# 16_ch_sample-and-hold_card_v4_1_1.net
KiCad netlist of a schematic drawn in EAGLE
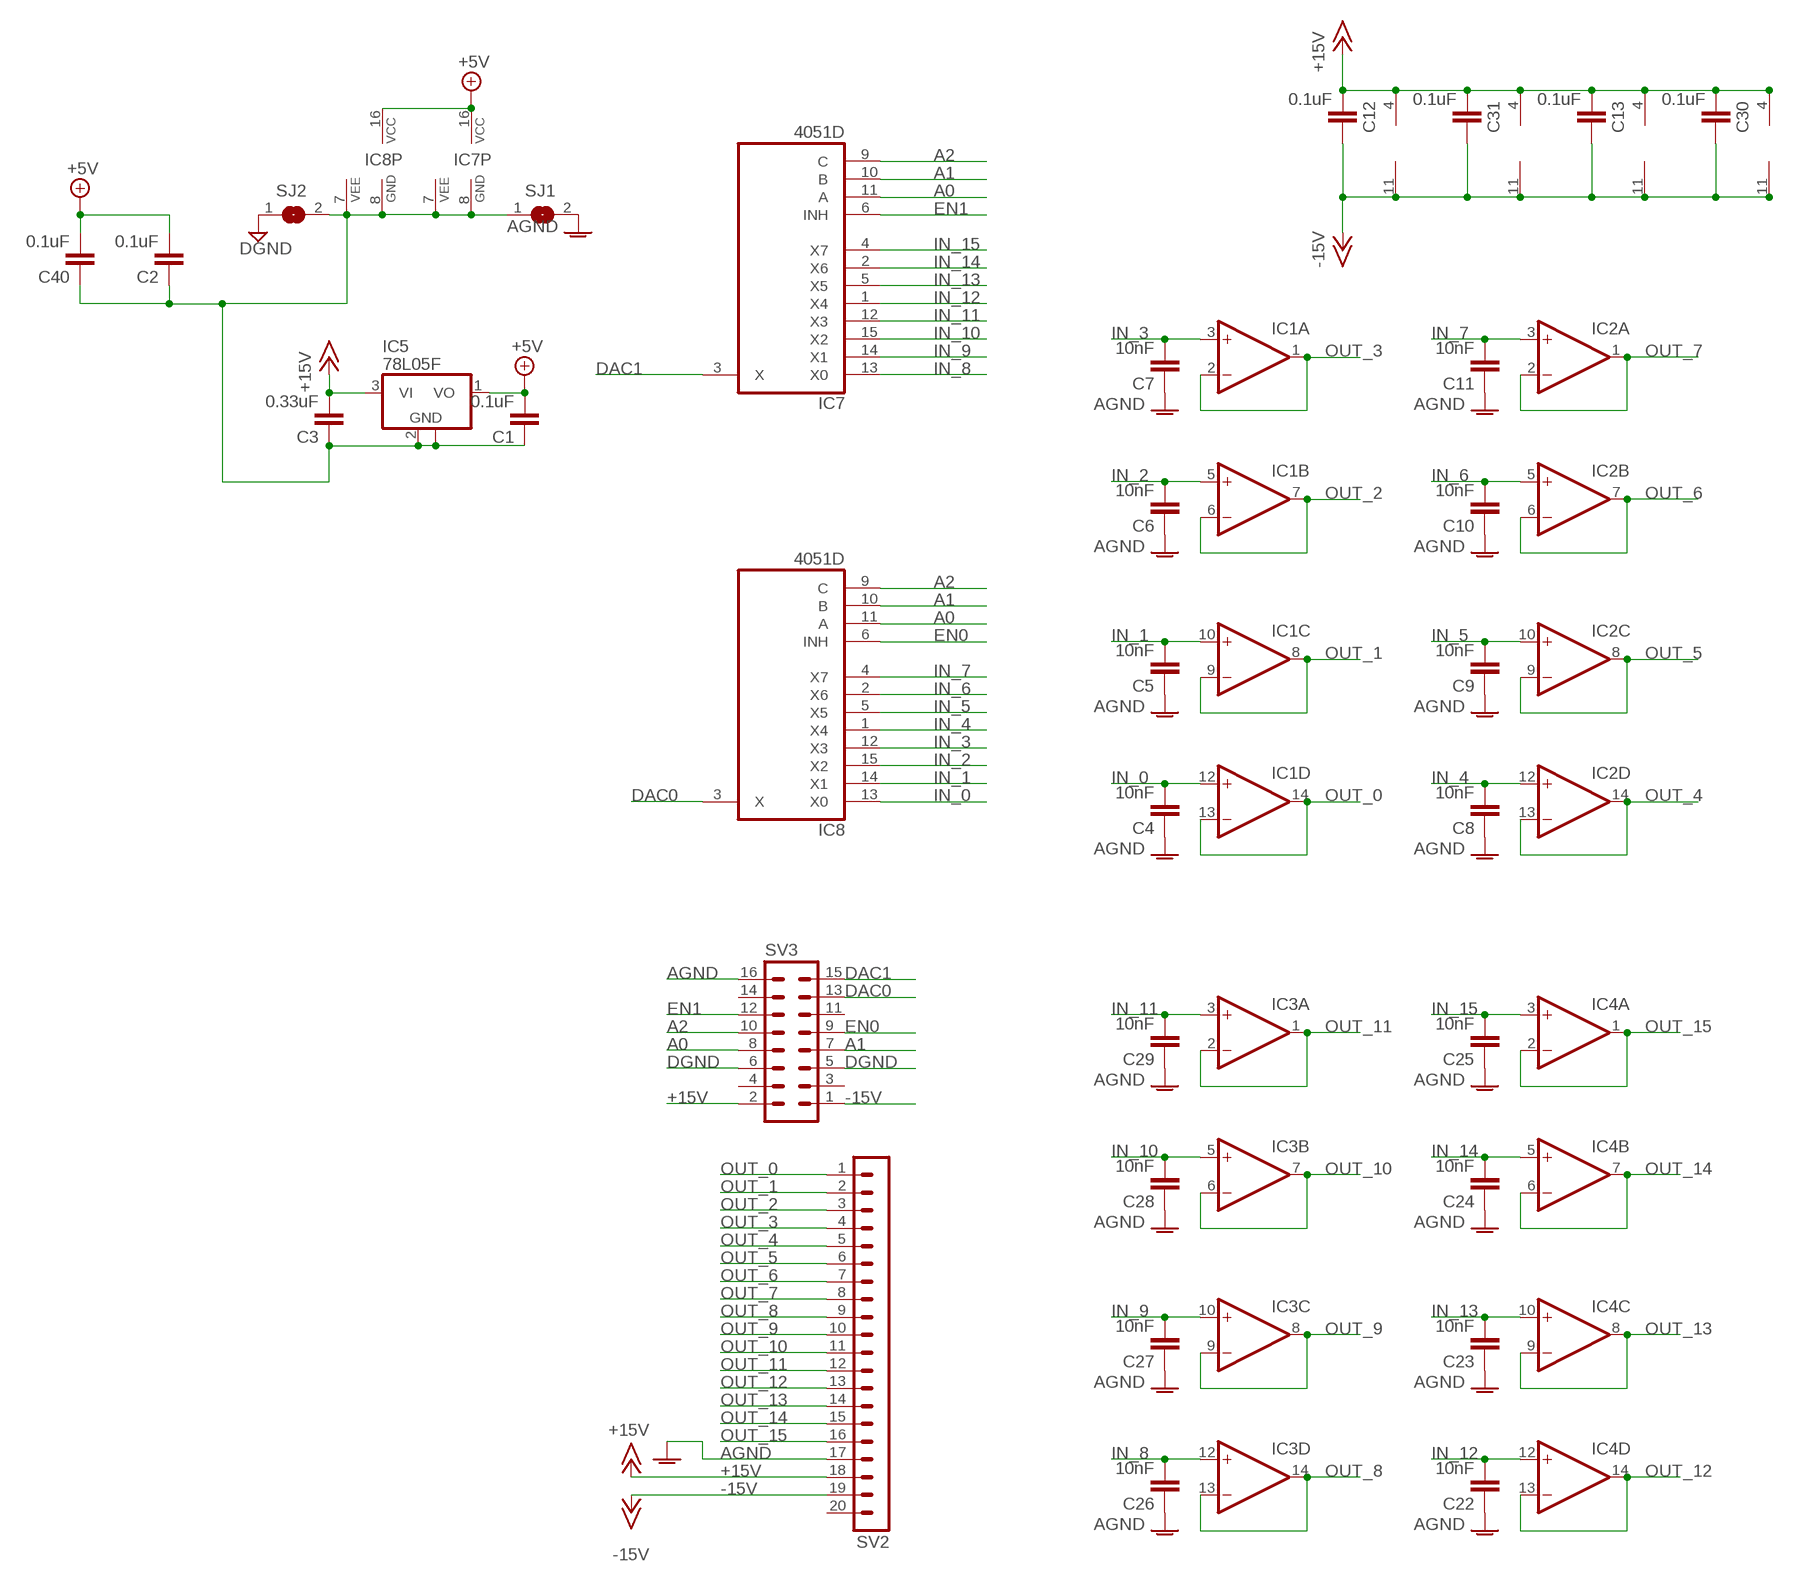
[diagram p0: schematic, sheet 1]

(export (version "E")
  (design (tool "Eeschema 10.0.6"))
  (components
    (comp (ref "C1")
      (value "0.1uF")
      (footprint "eagle-import:C0603")
      (libsource (lib "eagle-import") (part "resistor_C-EUC0603"))
    )
    (comp (ref "C2")
      (value "0.1uF")
      (footprint "eagle-import:C0603")
      (libsource (lib "eagle-import") (part "resistor_C-EUC0603"))
    )
    (comp (ref "C3")
      (value "0.33uF")
      (footprint "eagle-import:C0603")
      (libsource (lib "eagle-import") (part "resistor_C-EUC0603"))
    )
    (comp (ref "C4")
      (value "10nF")
      (footprint "eagle-import:C0805")
      (libsource (lib "eagle-import") (part "C-EUC0805"))
    )
    (comp (ref "C5")
      (value "10nF")
      (footprint "eagle-import:C0805")
      (libsource (lib "eagle-import") (part "C-EUC0805"))
    )
    (comp (ref "C6")
      (value "10nF")
      (footprint "eagle-import:C0805")
      (libsource (lib "eagle-import") (part "C-EUC0805"))
    )
    (comp (ref "C7")
      (value "10nF")
      (footprint "eagle-import:C0805")
      (libsource (lib "eagle-import") (part "C-EUC0805"))
    )
    (comp (ref "C8")
      (value "10nF")
      (footprint "eagle-import:C0805")
      (libsource (lib "eagle-import") (part "C-EUC0805"))
    )
    (comp (ref "C9")
      (value "10nF")
      (footprint "eagle-import:C0805")
      (libsource (lib "eagle-import") (part "C-EUC0805"))
    )
    (comp (ref "C10")
      (value "10nF")
      (footprint "eagle-import:C0805")
      (libsource (lib "eagle-import") (part "C-EUC0805"))
    )
    (comp (ref "C11")
      (value "10nF")
      (footprint "eagle-import:C0805")
      (libsource (lib "eagle-import") (part "C-EUC0805"))
    )
    (comp (ref "C12")
      (value "0.1uF")
      (footprint "eagle-import:C0603")
      (libsource (lib "eagle-import") (part "resistor_C-EUC0603"))
    )
    (comp (ref "C13")
      (value "0.1uF")
      (footprint "eagle-import:C0603")
      (libsource (lib "eagle-import") (part "resistor_C-EUC0603"))
    )
    (comp (ref "C22")
      (value "10nF")
      (footprint "eagle-import:C0805")
      (libsource (lib "eagle-import") (part "C-EUC0805"))
    )
    (comp (ref "C23")
      (value "10nF")
      (footprint "eagle-import:C0805")
      (libsource (lib "eagle-import") (part "C-EUC0805"))
    )
    (comp (ref "C24")
      (value "10nF")
      (footprint "eagle-import:C0805")
      (libsource (lib "eagle-import") (part "C-EUC0805"))
    )
    (comp (ref "C25")
      (value "10nF")
      (footprint "eagle-import:C0805")
      (libsource (lib "eagle-import") (part "C-EUC0805"))
    )
    (comp (ref "C26")
      (value "10nF")
      (footprint "eagle-import:C0805")
      (libsource (lib "eagle-import") (part "C-EUC0805"))
    )
    (comp (ref "C27")
      (value "10nF")
      (footprint "eagle-import:C0805")
      (libsource (lib "eagle-import") (part "C-EUC0805"))
    )
    (comp (ref "C28")
      (value "10nF")
      (footprint "eagle-import:C0805")
      (libsource (lib "eagle-import") (part "C-EUC0805"))
    )
    (comp (ref "C29")
      (value "10nF")
      (footprint "eagle-import:C0805")
      (libsource (lib "eagle-import") (part "C-EUC0805"))
    )
    (comp (ref "C30")
      (value "0.1uF")
      (footprint "eagle-import:C0603")
      (libsource (lib "eagle-import") (part "resistor_C-EUC0603"))
    )
    (comp (ref "C31")
      (value "0.1uF")
      (footprint "eagle-import:C0603")
      (libsource (lib "eagle-import") (part "resistor_C-EUC0603"))
    )
    (comp (ref "C40")
      (value "0.1uF")
      (footprint "eagle-import:C0603")
      (libsource (lib "eagle-import") (part "resistor_C-EUC0603"))
    )
    (comp (ref "IC1")
      (value "TL074D")
      (footprint "eagle-import:SO14")
      (libsource (lib "eagle-import") (part "TL074D"))
    )
    (comp (ref "IC2")
      (value "TL074D")
      (footprint "eagle-import:SO14")
      (libsource (lib "eagle-import") (part "TL074D"))
    )
    (comp (ref "IC3")
      (value "TL074D")
      (footprint "eagle-import:SO14")
      (libsource (lib "eagle-import") (part "TL074D"))
    )
    (comp (ref "IC4")
      (value "TL074D")
      (footprint "eagle-import:SO14")
      (libsource (lib "eagle-import") (part "TL074D"))
    )
    (comp (ref "IC5")
      (value "78L05F")
      (footprint "eagle-import:SOT89")
      (libsource (lib "eagle-import") (part "78LF05"))
    )
    (comp (ref "IC7")
      (value "4051D")
      (footprint "eagle-import:SO16")
      (libsource (lib "eagle-import") (part "4051D"))
    )
    (comp (ref "IC8")
      (value "4051D")
      (footprint "eagle-import:SO16")
      (libsource (lib "eagle-import") (part "4051D"))
    )
    (comp (ref "SJ1") (value "SJ") (footprint "eagle-import:SJ") (libsource (lib "eagle-import") (part "SJ")))
    (comp (ref "SJ2") (value "SJ") (footprint "eagle-import:SJ") (libsource (lib "eagle-import") (part "SJ")))
    (comp (ref "SV2")
      (value "MA20-1")
      (footprint "eagle-import:MA20-1")
      (libsource (lib "eagle-import") (part "MA20-1"))
    )
    (comp (ref "SV3")
      (value "MA08-2J")
      (footprint "eagle-import:MA08-2J")
      (libsource (lib "eagle-import") (part "MA08-2J"))
    )
  )
  (nets
    (net (code "1") (name "+5V") (class "Default")
      (node (ref "C1") (pin "2") (pinfunction "2_2") (pintype "passive"))
      (node (ref "C2") (pin "2") (pinfunction "2_2") (pintype "passive"))
      (node (ref "C40") (pin "2") (pinfunction "2_2") (pintype "passive"))
      (node (ref "IC5") (pin "1") (pinfunction "VO_1") (pintype "passive"))
      (node (ref "IC7") (pin "16") (pinfunction "VCC_16") (pintype "power_in"))
      (node (ref "IC8") (pin "16") (pinfunction "VCC_16") (pintype "power_in"))
    )
    (net (code "2") (name "+15V") (class "Default")
      (node (ref "C12") (pin "1") (pinfunction "1_1") (pintype "passive"))
      (node (ref "C13") (pin "1") (pinfunction "1_1") (pintype "passive"))
      (node (ref "C3") (pin "2") (pinfunction "2_2") (pintype "passive"))
      (node (ref "C30") (pin "1") (pinfunction "1_1") (pintype "passive"))
      (node (ref "C31") (pin "1") (pinfunction "1_1") (pintype "passive"))
      (node (ref "IC1") (pin "4") (pinfunction "V+_4") (pintype "power_in"))
      (node (ref "IC2") (pin "4") (pinfunction "V+_4") (pintype "power_in"))
      (node (ref "IC3") (pin "4") (pinfunction "V+_4") (pintype "power_in"))
      (node (ref "IC4") (pin "4") (pinfunction "V+_4") (pintype "power_in"))
      (node (ref "IC5") (pin "3") (pinfunction "VI_3") (pintype "input"))
      (node (ref "SV2") (pin "18") (pinfunction "18_18") (pintype "passive"))
      (node (ref "SV3") (pin "2") (pinfunction "2_2") (pintype "passive"))
    )
    (net (code "3") (name "-15V") (class "Default")
      (node (ref "C12") (pin "2") (pinfunction "2_2") (pintype "passive"))
      (node (ref "C13") (pin "2") (pinfunction "2_2") (pintype "passive"))
      (node (ref "C30") (pin "2") (pinfunction "2_2") (pintype "passive"))
      (node (ref "C31") (pin "2") (pinfunction "2_2") (pintype "passive"))
      (node (ref "IC1") (pin "11") (pinfunction "V-_11") (pintype "power_in"))
      (node (ref "IC2") (pin "11") (pinfunction "V-_11") (pintype "power_in"))
      (node (ref "IC3") (pin "11") (pinfunction "V-_11") (pintype "power_in"))
      (node (ref "IC4") (pin "11") (pinfunction "V-_11") (pintype "power_in"))
      (node (ref "SV2") (pin "19") (pinfunction "19_19") (pintype "passive"))
      (node (ref "SV3") (pin "1") (pinfunction "1_1") (pintype "passive"))
    )
    (net (code "4") (name "/A0") (class "Default")
      (node (ref "IC7") (pin "11") (pinfunction "A_11") (pintype "input"))
      (node (ref "IC8") (pin "11") (pinfunction "A_11") (pintype "input"))
      (node (ref "SV3") (pin "8") (pinfunction "8_8") (pintype "passive"))
    )
    (net (code "5") (name "/A1") (class "Default")
      (node (ref "IC7") (pin "10") (pinfunction "B_10") (pintype "input"))
      (node (ref "IC8") (pin "10") (pinfunction "B_10") (pintype "input"))
      (node (ref "SV3") (pin "7") (pinfunction "7_7") (pintype "passive"))
    )
    (net (code "6") (name "/A2") (class "Default")
      (node (ref "IC7") (pin "9") (pinfunction "C_9") (pintype "input"))
      (node (ref "IC8") (pin "9") (pinfunction "C_9") (pintype "input"))
      (node (ref "SV3") (pin "10") (pinfunction "10_10") (pintype "passive"))
    )
    (net (code "7") (name "/DAC0") (class "Default")
      (node (ref "IC8") (pin "3") (pinfunction "X_3") (pintype "bidirectional"))
      (node (ref "SV3") (pin "13") (pinfunction "13_13") (pintype "passive"))
    )
    (net (code "8") (name "/DAC1") (class "Default")
      (node (ref "IC7") (pin "3") (pinfunction "X_3") (pintype "bidirectional"))
      (node (ref "SV3") (pin "15") (pinfunction "15_15") (pintype "passive"))
    )
    (net (code "9") (name "/EN0") (class "Default")
      (node (ref "IC8") (pin "6") (pinfunction "INH_6") (pintype "input"))
      (node (ref "SV3") (pin "9") (pinfunction "9_9") (pintype "passive"))
    )
    (net (code "10") (name "/EN1") (class "Default")
      (node (ref "IC7") (pin "6") (pinfunction "INH_6") (pintype "input"))
      (node (ref "SV3") (pin "12") (pinfunction "12_12") (pintype "passive"))
    )
    (net (code "11") (name "/IN_0") (class "Default")
      (node (ref "C4") (pin "2") (pinfunction "2_2") (pintype "passive"))
      (node (ref "IC1") (pin "12") (pinfunction "+IN_12") (pintype "input"))
      (node (ref "IC8") (pin "13") (pinfunction "X0_13") (pintype "bidirectional"))
    )
    (net (code "12") (name "/IN_1") (class "Default")
      (node (ref "C5") (pin "2") (pinfunction "2_2") (pintype "passive"))
      (node (ref "IC1") (pin "10") (pinfunction "+IN_10") (pintype "input"))
      (node (ref "IC8") (pin "14") (pinfunction "X1_14") (pintype "bidirectional"))
    )
    (net (code "13") (name "/IN_2") (class "Default")
      (node (ref "C6") (pin "2") (pinfunction "2_2") (pintype "passive"))
      (node (ref "IC1") (pin "5") (pinfunction "+IN_5") (pintype "input"))
      (node (ref "IC8") (pin "15") (pinfunction "X2_15") (pintype "bidirectional"))
    )
    (net (code "14") (name "/IN_3") (class "Default")
      (node (ref "C7") (pin "2") (pinfunction "2_2") (pintype "passive"))
      (node (ref "IC1") (pin "3") (pinfunction "+IN_3") (pintype "input"))
      (node (ref "IC8") (pin "12") (pinfunction "X3_12") (pintype "bidirectional"))
    )
    (net (code "15") (name "/IN_4") (class "Default")
      (node (ref "C8") (pin "2") (pinfunction "2_2") (pintype "passive"))
      (node (ref "IC2") (pin "12") (pinfunction "+IN_12") (pintype "input"))
      (node (ref "IC8") (pin "1") (pinfunction "X4_1") (pintype "bidirectional"))
    )
    (net (code "16") (name "/IN_5") (class "Default")
      (node (ref "C9") (pin "2") (pinfunction "2_2") (pintype "passive"))
      (node (ref "IC2") (pin "10") (pinfunction "+IN_10") (pintype "input"))
      (node (ref "IC8") (pin "5") (pinfunction "X5_5") (pintype "bidirectional"))
    )
    (net (code "17") (name "/IN_6") (class "Default")
      (node (ref "C10") (pin "2") (pinfunction "2_2") (pintype "passive"))
      (node (ref "IC2") (pin "5") (pinfunction "+IN_5") (pintype "input"))
      (node (ref "IC8") (pin "2") (pinfunction "X6_2") (pintype "bidirectional"))
    )
    (net (code "18") (name "/IN_7") (class "Default")
      (node (ref "C11") (pin "2") (pinfunction "2_2") (pintype "passive"))
      (node (ref "IC2") (pin "3") (pinfunction "+IN_3") (pintype "input"))
      (node (ref "IC8") (pin "4") (pinfunction "X7_4") (pintype "bidirectional"))
    )
    (net (code "19") (name "/IN_8") (class "Default")
      (node (ref "C26") (pin "2") (pinfunction "2_2") (pintype "passive"))
      (node (ref "IC3") (pin "12") (pinfunction "+IN_12") (pintype "input"))
      (node (ref "IC7") (pin "13") (pinfunction "X0_13") (pintype "bidirectional"))
    )
    (net (code "20") (name "/IN_9") (class "Default")
      (node (ref "C27") (pin "2") (pinfunction "2_2") (pintype "passive"))
      (node (ref "IC3") (pin "10") (pinfunction "+IN_10") (pintype "input"))
      (node (ref "IC7") (pin "14") (pinfunction "X1_14") (pintype "bidirectional"))
    )
    (net (code "21") (name "/IN_10") (class "Default")
      (node (ref "C28") (pin "2") (pinfunction "2_2") (pintype "passive"))
      (node (ref "IC3") (pin "5") (pinfunction "+IN_5") (pintype "input"))
      (node (ref "IC7") (pin "15") (pinfunction "X2_15") (pintype "bidirectional"))
    )
    (net (code "22") (name "/IN_11") (class "Default")
      (node (ref "C29") (pin "2") (pinfunction "2_2") (pintype "passive"))
      (node (ref "IC3") (pin "3") (pinfunction "+IN_3") (pintype "input"))
      (node (ref "IC7") (pin "12") (pinfunction "X3_12") (pintype "bidirectional"))
    )
    (net (code "23") (name "/IN_12") (class "Default")
      (node (ref "C22") (pin "2") (pinfunction "2_2") (pintype "passive"))
      (node (ref "IC4") (pin "12") (pinfunction "+IN_12") (pintype "input"))
      (node (ref "IC7") (pin "1") (pinfunction "X4_1") (pintype "bidirectional"))
    )
    (net (code "24") (name "/IN_13") (class "Default")
      (node (ref "C23") (pin "2") (pinfunction "2_2") (pintype "passive"))
      (node (ref "IC4") (pin "10") (pinfunction "+IN_10") (pintype "input"))
      (node (ref "IC7") (pin "5") (pinfunction "X5_5") (pintype "bidirectional"))
    )
    (net (code "25") (name "/IN_14") (class "Default")
      (node (ref "C24") (pin "2") (pinfunction "2_2") (pintype "passive"))
      (node (ref "IC4") (pin "5") (pinfunction "+IN_5") (pintype "input"))
      (node (ref "IC7") (pin "2") (pinfunction "X6_2") (pintype "bidirectional"))
    )
    (net (code "26") (name "/IN_15") (class "Default")
      (node (ref "C25") (pin "2") (pinfunction "2_2") (pintype "passive"))
      (node (ref "IC4") (pin "3") (pinfunction "+IN_3") (pintype "input"))
      (node (ref "IC7") (pin "4") (pinfunction "X7_4") (pintype "bidirectional"))
    )
    (net (code "27") (name "/OUT_0") (class "Default")
      (node (ref "IC1") (pin "13") (pinfunction "-IN_13") (pintype "input"))
      (node (ref "IC1") (pin "14") (pinfunction "OUT_14") (pintype "output"))
      (node (ref "SV2") (pin "1") (pinfunction "1_1") (pintype "passive"))
    )
    (net (code "28") (name "/OUT_1") (class "Default")
      (node (ref "IC1") (pin "8") (pinfunction "OUT_8") (pintype "output"))
      (node (ref "IC1") (pin "9") (pinfunction "-IN_9") (pintype "input"))
      (node (ref "SV2") (pin "2") (pinfunction "2_2") (pintype "passive"))
    )
    (net (code "29") (name "/OUT_2") (class "Default")
      (node (ref "IC1") (pin "6") (pinfunction "-IN_6") (pintype "input"))
      (node (ref "IC1") (pin "7") (pinfunction "OUT_7") (pintype "output"))
      (node (ref "SV2") (pin "3") (pinfunction "3_3") (pintype "passive"))
    )
    (net (code "30") (name "/OUT_3") (class "Default")
      (node (ref "IC1") (pin "1") (pinfunction "OUT_1") (pintype "output"))
      (node (ref "IC1") (pin "2") (pinfunction "-IN_2") (pintype "input"))
      (node (ref "SV2") (pin "4") (pinfunction "4_4") (pintype "passive"))
    )
    (net (code "31") (name "/OUT_4") (class "Default")
      (node (ref "IC2") (pin "13") (pinfunction "-IN_13") (pintype "input"))
      (node (ref "IC2") (pin "14") (pinfunction "OUT_14") (pintype "output"))
      (node (ref "SV2") (pin "5") (pinfunction "5_5") (pintype "passive"))
    )
    (net (code "32") (name "/OUT_5") (class "Default")
      (node (ref "IC2") (pin "8") (pinfunction "OUT_8") (pintype "output"))
      (node (ref "IC2") (pin "9") (pinfunction "-IN_9") (pintype "input"))
      (node (ref "SV2") (pin "6") (pinfunction "6_6") (pintype "passive"))
    )
    (net (code "33") (name "/OUT_6") (class "Default")
      (node (ref "IC2") (pin "6") (pinfunction "-IN_6") (pintype "input"))
      (node (ref "IC2") (pin "7") (pinfunction "OUT_7") (pintype "output"))
      (node (ref "SV2") (pin "7") (pinfunction "7_7") (pintype "passive"))
    )
    (net (code "34") (name "/OUT_7") (class "Default")
      (node (ref "IC2") (pin "1") (pinfunction "OUT_1") (pintype "output"))
      (node (ref "IC2") (pin "2") (pinfunction "-IN_2") (pintype "input"))
      (node (ref "SV2") (pin "8") (pinfunction "8_8") (pintype "passive"))
    )
    (net (code "35") (name "/OUT_8") (class "Default")
      (node (ref "IC3") (pin "13") (pinfunction "-IN_13") (pintype "input"))
      (node (ref "IC3") (pin "14") (pinfunction "OUT_14") (pintype "output"))
      (node (ref "SV2") (pin "9") (pinfunction "9_9") (pintype "passive"))
    )
    (net (code "36") (name "/OUT_9") (class "Default")
      (node (ref "IC3") (pin "8") (pinfunction "OUT_8") (pintype "output"))
      (node (ref "IC3") (pin "9") (pinfunction "-IN_9") (pintype "input"))
      (node (ref "SV2") (pin "10") (pinfunction "10_10") (pintype "passive"))
    )
    (net (code "37") (name "/OUT_10") (class "Default")
      (node (ref "IC3") (pin "6") (pinfunction "-IN_6") (pintype "input"))
      (node (ref "IC3") (pin "7") (pinfunction "OUT_7") (pintype "output"))
      (node (ref "SV2") (pin "11") (pinfunction "11_11") (pintype "passive"))
    )
    (net (code "38") (name "/OUT_11") (class "Default")
      (node (ref "IC3") (pin "1") (pinfunction "OUT_1") (pintype "output"))
      (node (ref "IC3") (pin "2") (pinfunction "-IN_2") (pintype "input"))
      (node (ref "SV2") (pin "12") (pinfunction "12_12") (pintype "passive"))
    )
    (net (code "39") (name "/OUT_12") (class "Default")
      (node (ref "IC4") (pin "13") (pinfunction "-IN_13") (pintype "input"))
      (node (ref "IC4") (pin "14") (pinfunction "OUT_14") (pintype "output"))
      (node (ref "SV2") (pin "13") (pinfunction "13_13") (pintype "passive"))
    )
    (net (code "40") (name "/OUT_13") (class "Default")
      (node (ref "IC4") (pin "8") (pinfunction "OUT_8") (pintype "output"))
      (node (ref "IC4") (pin "9") (pinfunction "-IN_9") (pintype "input"))
      (node (ref "SV2") (pin "14") (pinfunction "14_14") (pintype "passive"))
    )
    (net (code "41") (name "/OUT_14") (class "Default")
      (node (ref "IC4") (pin "6") (pinfunction "-IN_6") (pintype "input"))
      (node (ref "IC4") (pin "7") (pinfunction "OUT_7") (pintype "output"))
      (node (ref "SV2") (pin "15") (pinfunction "15_15") (pintype "passive"))
    )
    (net (code "42") (name "/OUT_15") (class "Default")
      (node (ref "IC4") (pin "1") (pinfunction "OUT_1") (pintype "output"))
      (node (ref "IC4") (pin "2") (pinfunction "-IN_2") (pintype "input"))
      (node (ref "SV2") (pin "16") (pinfunction "16_16") (pintype "passive"))
    )
    (net (code "43") (name "AGND") (class "Default")
      (node (ref "C10") (pin "1") (pinfunction "1_1") (pintype "passive"))
      (node (ref "C11") (pin "1") (pinfunction "1_1") (pintype "passive"))
      (node (ref "C22") (pin "1") (pinfunction "1_1") (pintype "passive"))
      (node (ref "C23") (pin "1") (pinfunction "1_1") (pintype "passive"))
      (node (ref "C24") (pin "1") (pinfunction "1_1") (pintype "passive"))
      (node (ref "C25") (pin "1") (pinfunction "1_1") (pintype "passive"))
      (node (ref "C26") (pin "1") (pinfunction "1_1") (pintype "passive"))
      (node (ref "C27") (pin "1") (pinfunction "1_1") (pintype "passive"))
      (node (ref "C28") (pin "1") (pinfunction "1_1") (pintype "passive"))
      (node (ref "C29") (pin "1") (pinfunction "1_1") (pintype "passive"))
      (node (ref "C4") (pin "1") (pinfunction "1_1") (pintype "passive"))
      (node (ref "C5") (pin "1") (pinfunction "1_1") (pintype "passive"))
      (node (ref "C6") (pin "1") (pinfunction "1_1") (pintype "passive"))
      (node (ref "C7") (pin "1") (pinfunction "1_1") (pintype "passive"))
      (node (ref "C8") (pin "1") (pinfunction "1_1") (pintype "passive"))
      (node (ref "C9") (pin "1") (pinfunction "1_1") (pintype "passive"))
      (node (ref "SJ1") (pin "2") (pinfunction "2_2") (pintype "passive"))
      (node (ref "SV2") (pin "17") (pinfunction "17_17") (pintype "passive"))
      (node (ref "SV3") (pin "16") (pinfunction "16_16") (pintype "passive"))
    )
    (net (code "44") (name "DGND") (class "Default")
      (node (ref "SJ2") (pin "1") (pinfunction "1_1") (pintype "passive"))
      (node (ref "SV3") (pin "5") (pinfunction "5_5") (pintype "passive"))
      (node (ref "SV3") (pin "6") (pinfunction "6_6") (pintype "passive"))
    )
    (net (code "45") (name "Net-(IC7B-GND)") (class "Default")
      (node (ref "C1") (pin "1") (pinfunction "1_1") (pintype "passive"))
      (node (ref "C2") (pin "1") (pinfunction "1_1") (pintype "passive"))
      (node (ref "C3") (pin "1") (pinfunction "1_1") (pintype "passive"))
      (node (ref "C40") (pin "1") (pinfunction "1_1") (pintype "passive"))
      (node (ref "IC5") (pin "2") (pinfunction "GND_2") (pintype "passive"))
      (node (ref "IC5") (pin "2@1") (pinfunction "GND_2@1") (pintype "passive"))
      (node (ref "IC7") (pin "7") (pinfunction "VEE_7") (pintype "power_in"))
      (node (ref "IC7") (pin "8") (pinfunction "GND_8") (pintype "power_in"))
      (node (ref "IC8") (pin "7") (pinfunction "VEE_7") (pintype "power_in"))
      (node (ref "IC8") (pin "8") (pinfunction "GND_8") (pintype "power_in"))
      (node (ref "SJ1") (pin "1") (pinfunction "1_1") (pintype "passive"))
      (node (ref "SJ2") (pin "2") (pinfunction "2_2") (pintype "passive"))
    )
    (net (code "46") (name "unconnected-(SV2-Pad20)") (class "Default")
      (node (ref "SV2") (pin "20") (pinfunction "20_20") (pintype "passive"))
    )
    (net (code "47") (name "unconnected-(SV3-Pad3)") (class "Default")
      (node (ref "SV3") (pin "3") (pinfunction "3_3") (pintype "passive"))
    )
    (net (code "48") (name "unconnected-(SV3-Pad4)") (class "Default")
      (node (ref "SV3") (pin "4") (pinfunction "4_4") (pintype "passive"))
    )
    (net (code "49") (name "unconnected-(SV3-Pad11)") (class "Default")
      (node (ref "SV3") (pin "11") (pinfunction "11_11") (pintype "passive"))
    )
    (net (code "50") (name "unconnected-(SV3-Pad14)") (class "Default")
      (node (ref "SV3") (pin "14") (pinfunction "14_14") (pintype "passive"))
    )
  )
)
